# cbr250r_license_light.net
KiCad netlist of a schematic drawn in EAGLE
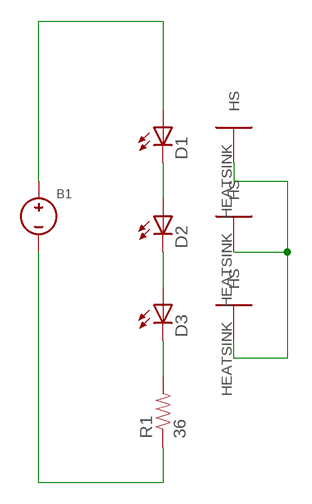
[diagram p0: schematic, sheet 1]

(export (version "E")
  (design (tool "Eeschema 10.0.6"))
  (components
    (comp (ref "B1")
      (value "168_BULBLIGHT_DOWN")
      (footprint "eagle-import:168_BULB")
      (libsource (lib "eagle-import") (part "168_BULBLIGHT_DOWN"))
    )
    (comp (ref "D1")
      (value "LED_HEATSINK4-SMD")
      (footprint "eagle-import:4-SMD")
      (libsource (lib "eagle-import") (part "LED_HEATSINK4-SMD"))
    )
    (comp (ref "D2")
      (value "LED_HEATSINK4-SMD")
      (footprint "eagle-import:4-SMD")
      (libsource (lib "eagle-import") (part "LED_HEATSINK4-SMD"))
    )
    (comp (ref "D3")
      (value "LED_HEATSINK4-SMD")
      (footprint "eagle-import:4-SMD")
      (libsource (lib "eagle-import") (part "LED_HEATSINK4-SMD"))
    )
    (comp (ref "R1")
      (value "36")
      (footprint "eagle-import:R2010")
      (libsource (lib "eagle-import") (part "RESISTOR2010"))
    )
  )
  (nets
    (net (code "1") (name "Net-(B1-+-Pad1A)") (class "Default")
      (node (ref "B1") (pin "1A") (pinfunction "+_1A") (pintype "bidirectional"))
      (node (ref "B1") (pin "1B") (pinfunction "+_1B") (pintype "bidirectional"))
      (node (ref "D1") (pin "ANO1") (pinfunction "A_ANO1") (pintype "passive"))
      (node (ref "D1") (pin "ANO2") (pinfunction "A_ANO2") (pintype "passive"))
    )
    (net (code "2") (name "Net-(B1---Pad2A)") (class "Default")
      (node (ref "B1") (pin "2A") (pinfunction "-_2A") (pintype "bidirectional"))
      (node (ref "B1") (pin "2B") (pinfunction "-_2B") (pintype "bidirectional"))
      (node (ref "R1") (pin "1") (pinfunction "1_1") (pintype "passive"))
    )
    (net (code "3") (name "Net-(D1-C-PadCAT1)") (class "Default")
      (node (ref "D1") (pin "CAT1") (pinfunction "C_CAT1") (pintype "passive"))
      (node (ref "D1") (pin "CAT2") (pinfunction "C_CAT2") (pintype "passive"))
      (node (ref "D2") (pin "ANO1") (pinfunction "A_ANO1") (pintype "passive"))
      (node (ref "D2") (pin "ANO2") (pinfunction "A_ANO2") (pintype "passive"))
    )
    (net (code "4") (name "Net-(D1-HS)") (class "Default")
      (node (ref "D1") (pin "HEATSINK") (pinfunction "HS_HEATSINK") (pintype "bidirectional"))
      (node (ref "D2") (pin "HEATSINK") (pinfunction "HS_HEATSINK") (pintype "bidirectional"))
      (node (ref "D3") (pin "HEATSINK") (pinfunction "HS_HEATSINK") (pintype "bidirectional"))
    )
    (net (code "5") (name "Net-(D2-C-PadCAT1)") (class "Default")
      (node (ref "D2") (pin "CAT1") (pinfunction "C_CAT1") (pintype "passive"))
      (node (ref "D2") (pin "CAT2") (pinfunction "C_CAT2") (pintype "passive"))
      (node (ref "D3") (pin "ANO1") (pinfunction "A_ANO1") (pintype "passive"))
      (node (ref "D3") (pin "ANO2") (pinfunction "A_ANO2") (pintype "passive"))
    )
    (net (code "6") (name "Net-(D3-C-PadCAT1)") (class "Default")
      (node (ref "D3") (pin "CAT1") (pinfunction "C_CAT1") (pintype "passive"))
      (node (ref "D3") (pin "CAT2") (pinfunction "C_CAT2") (pintype "passive"))
      (node (ref "R1") (pin "2") (pinfunction "2_2") (pintype "passive"))
    )
  )
)
